# Lamp_dispatcher.net
KiCad netlist of a schematic drawn in EAGLE
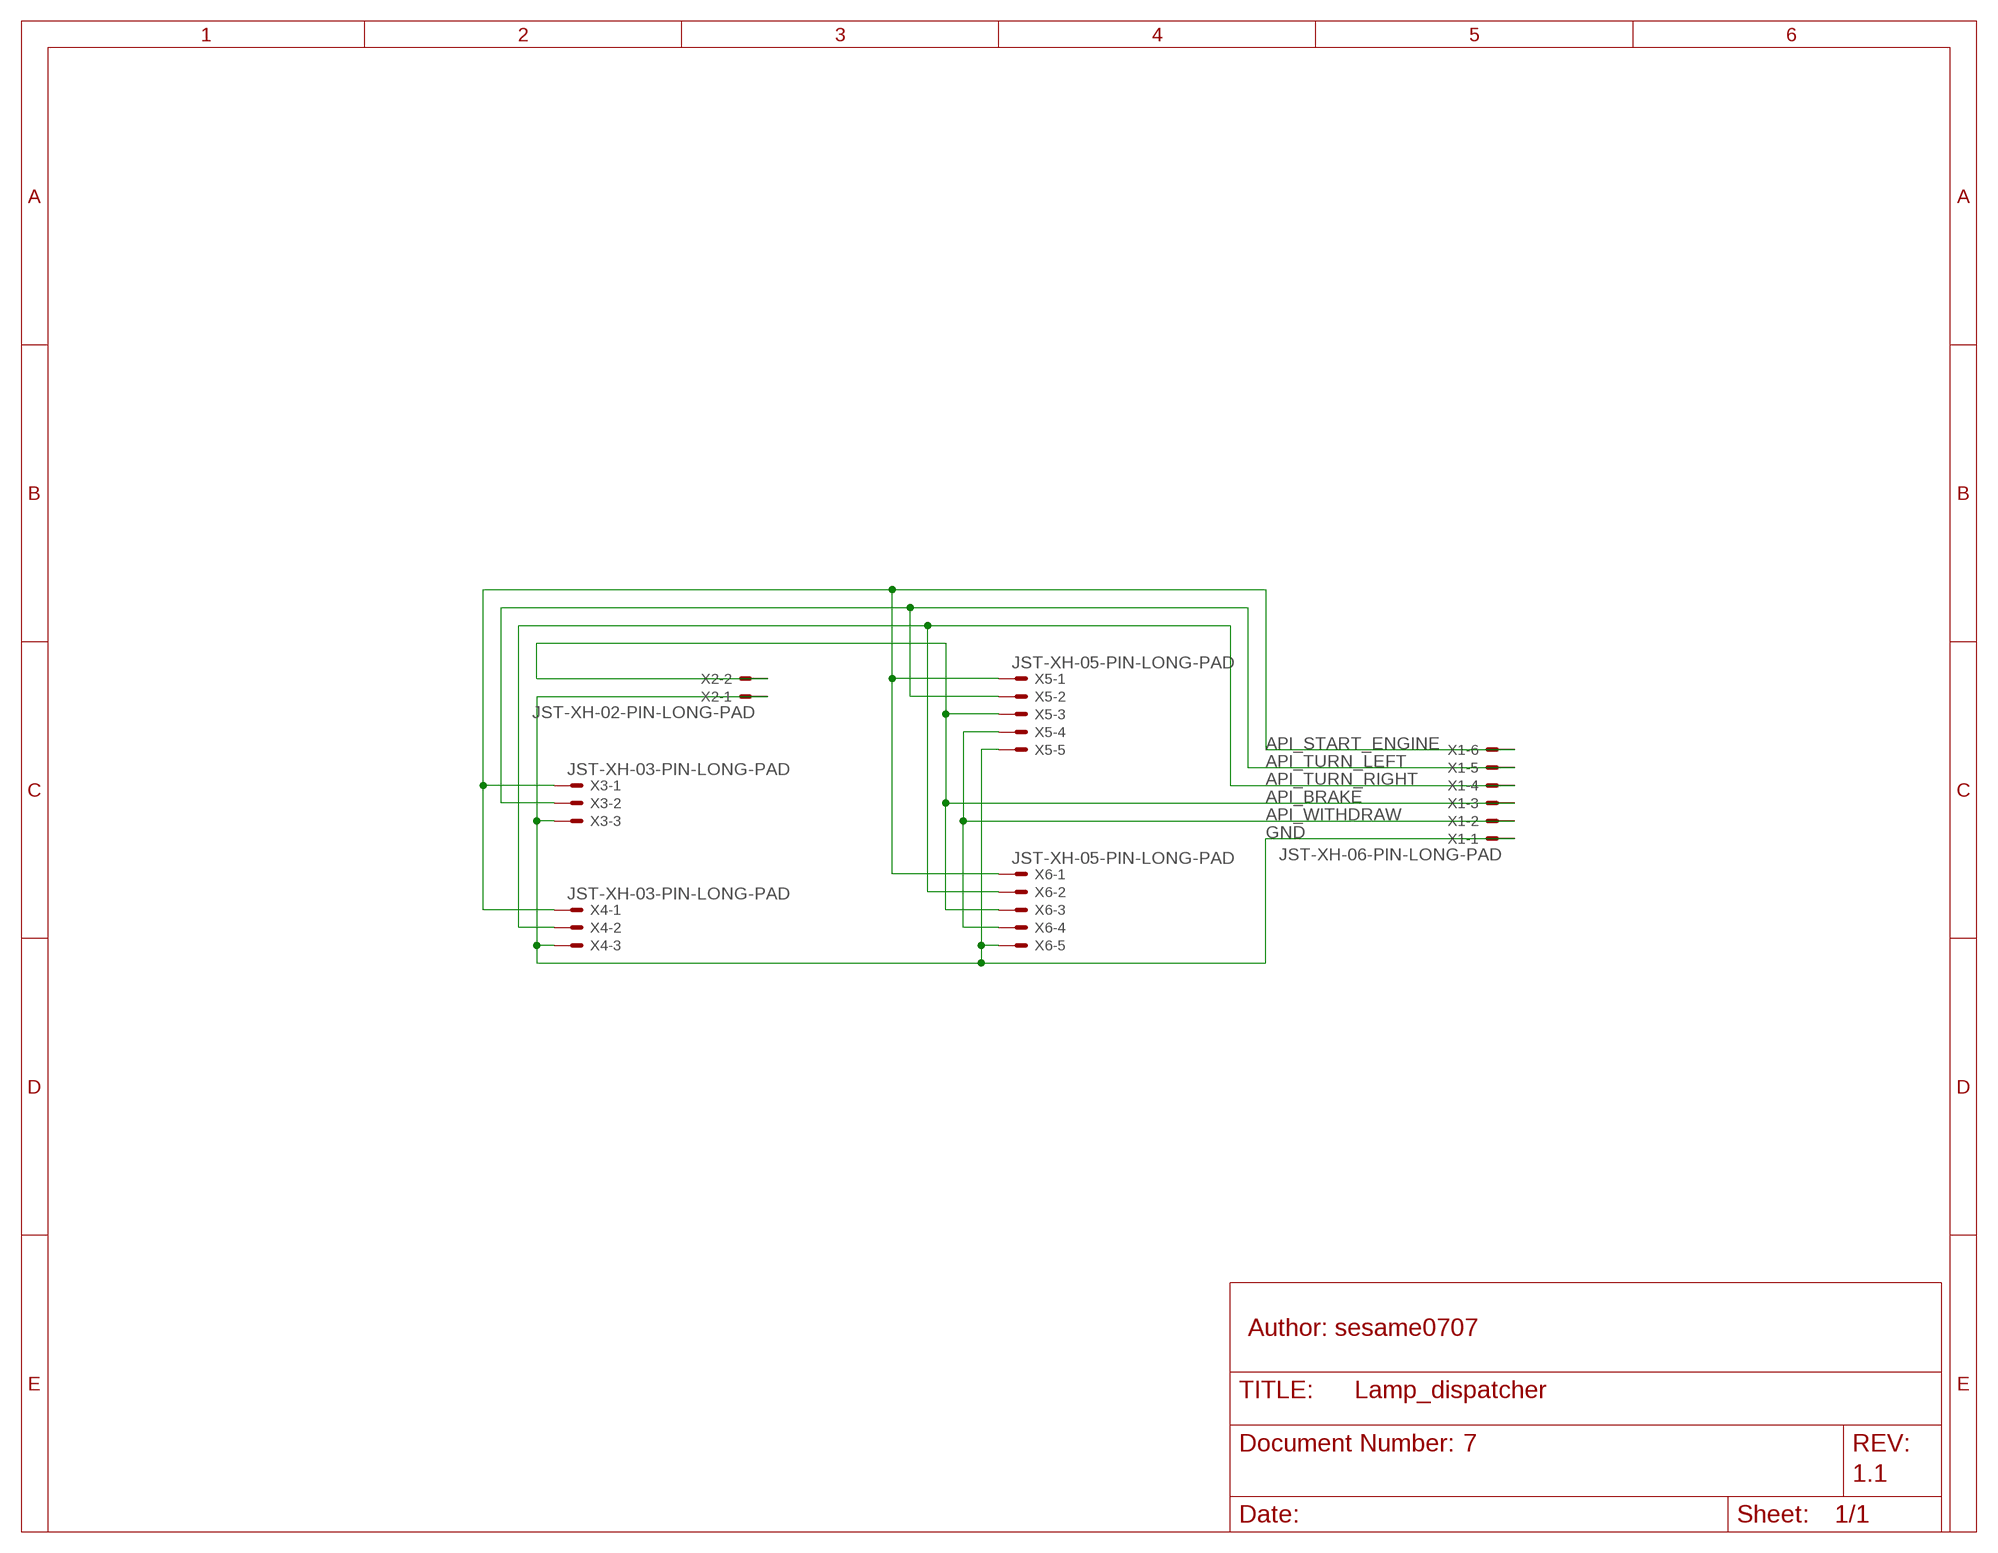
[diagram p0: schematic, sheet 1]

(export (version "E")
  (design (tool "Eeschema 10.0.6"))
  (components
    (comp (ref "X1")
      (value "JST-XH-06-PIN-LONG-PAD")
      (footprint "eagle-import:JST-XH-06-PACKAGE-LONG-PAD")
      (libsource (lib "eagle-import") (part "JST-XH-06-PIN-LONG-PAD"))
    )
    (comp (ref "X2")
      (value "JST-XH-02-PIN-LONG-PAD")
      (footprint "eagle-import:JST-XH-02-PACKAGE-LONG-PAD")
      (libsource (lib "eagle-import") (part "JST-XH-02-PIN-LONG-PAD"))
    )
    (comp (ref "X3")
      (value "JST-XH-03-PIN-LONG-PAD")
      (footprint "eagle-import:JST-XH-03-PACKAGE-LONG-PAD")
      (libsource (lib "eagle-import") (part "JST-XH-03-PIN-LONG-PAD"))
    )
    (comp (ref "X4")
      (value "JST-XH-03-PIN-LONG-PAD")
      (footprint "eagle-import:JST-XH-03-PACKAGE-LONG-PAD")
      (libsource (lib "eagle-import") (part "JST-XH-03-PIN-LONG-PAD"))
    )
    (comp (ref "X5")
      (value "JST-XH-05-PIN-LONG-PAD")
      (footprint "eagle-import:JST-XH-05-PACKAGE-LONG-PAD")
      (libsource (lib "eagle-import") (part "JST-XH-05-PIN-LONG-PAD"))
    )
    (comp (ref "X6")
      (value "JST-XH-05-PIN-LONG-PAD")
      (footprint "eagle-import:JST-XH-05-PACKAGE-LONG-PAD")
      (libsource (lib "eagle-import") (part "JST-XH-05-PIN-LONG-PAD"))
    )
  )
  (nets
    (net (code "1") (name "/API_BRAKE") (class "Default")
      (node (ref "X1") (pin "3") (pinfunction "S_3") (pintype "passive"))
      (node (ref "X2") (pin "2") (pinfunction "S_2") (pintype "passive"))
      (node (ref "X5") (pin "3") (pinfunction "S_3") (pintype "passive"))
      (node (ref "X6") (pin "3") (pinfunction "S_3") (pintype "passive"))
    )
    (net (code "2") (name "/API_START_ENGINE") (class "Default")
      (node (ref "X1") (pin "6") (pinfunction "S_6") (pintype "passive"))
      (node (ref "X3") (pin "1") (pinfunction "S_1") (pintype "passive"))
      (node (ref "X4") (pin "1") (pinfunction "S_1") (pintype "passive"))
      (node (ref "X5") (pin "1") (pinfunction "S_1") (pintype "passive"))
      (node (ref "X6") (pin "1") (pinfunction "S_1") (pintype "passive"))
    )
    (net (code "3") (name "/API_TURN_LEFT") (class "Default")
      (node (ref "X1") (pin "5") (pinfunction "S_5") (pintype "passive"))
      (node (ref "X3") (pin "2") (pinfunction "S_2") (pintype "passive"))
      (node (ref "X5") (pin "2") (pinfunction "S_2") (pintype "passive"))
    )
    (net (code "4") (name "/API_TURN_RIGHT") (class "Default")
      (node (ref "X1") (pin "4") (pinfunction "S_4") (pintype "passive"))
      (node (ref "X4") (pin "2") (pinfunction "S_2") (pintype "passive"))
      (node (ref "X6") (pin "2") (pinfunction "S_2") (pintype "passive"))
    )
    (net (code "5") (name "/API_WITHDRAW") (class "Default")
      (node (ref "X1") (pin "2") (pinfunction "S_2") (pintype "passive"))
      (node (ref "X5") (pin "4") (pinfunction "S_4") (pintype "passive"))
      (node (ref "X6") (pin "4") (pinfunction "S_4") (pintype "passive"))
    )
    (net (code "6") (name "/GND") (class "Default")
      (node (ref "X1") (pin "1") (pinfunction "S_1") (pintype "passive"))
      (node (ref "X2") (pin "1") (pinfunction "S_1") (pintype "passive"))
      (node (ref "X3") (pin "3") (pinfunction "S_3") (pintype "passive"))
      (node (ref "X4") (pin "3") (pinfunction "S_3") (pintype "passive"))
      (node (ref "X5") (pin "5") (pinfunction "S_5") (pintype "passive"))
      (node (ref "X6") (pin "5") (pinfunction "S_5") (pintype "passive"))
    )
  )
)
